# Sheet1.net
KiCad netlist of a schematic drawn in Altium Designer
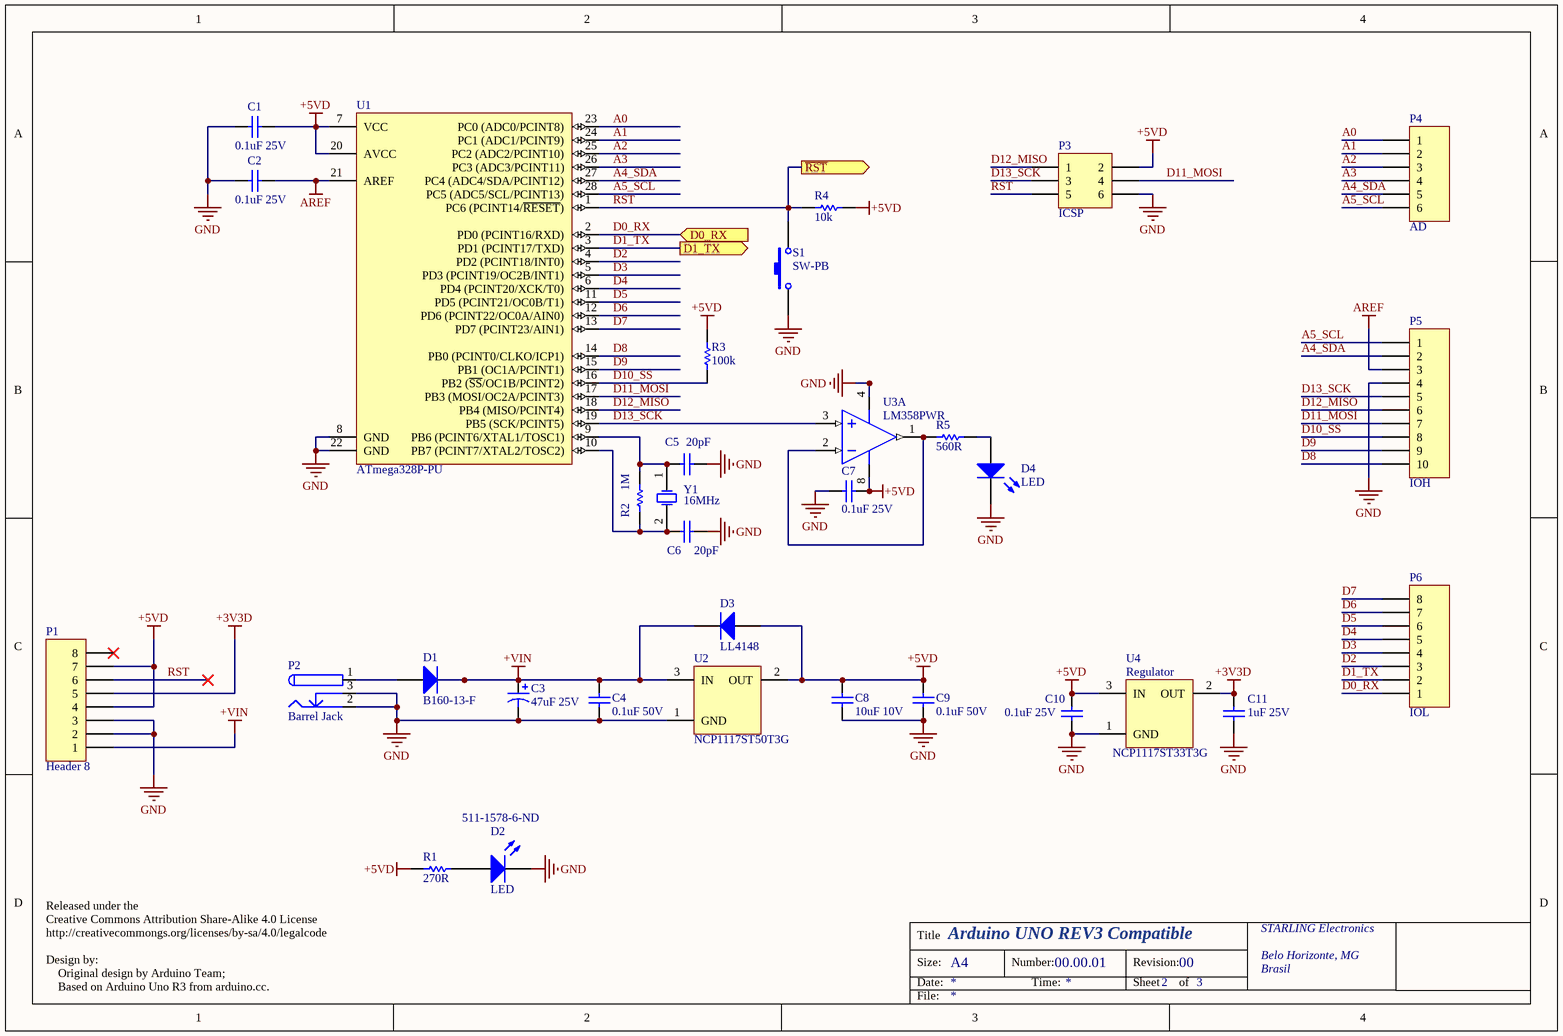
[diagram p0: Sheet1.SchDoc]

(export (version "E")
  (design (tool "Eeschema 10.0.6"))
  (components
    (comp (ref "C1")
      (value "0.1uF 25V")
      (footprint "C1608[0603]")
      (description "Capacitor")
      (fields (field (name "MANUFACTURER PART NUMBER") "GCM188R71E104KA57D") (field (name "TOLERANCE") "10%"))
      (libsource (lib "Basic Library") (part "C"))
    )
    (comp (ref "C2")
      (value "0.1uF 25V")
      (footprint "C1608[0603]")
      (description "Capacitor")
      (fields (field (name "MANUFACTURER PART NUMBER") "GCM188R71E104KA57D") (field (name "TOLERANCE") "10%"))
      (libsource (lib "Basic Library") (part "C"))
    )
    (comp (ref "C3")
      (value "47uF 25V")
      (footprint "Cap_Al_SMD_C6_6.6x6.6mm")
      (description "Polarized Capacitor")
      (fields (field (name "MANUFACTURER PART NUMBER") "EEE-1EA470WP") (field (name "TOLERANCE") "20%"))
      (libsource (lib "Basic Library") (part "CP"))
    )
    (comp (ref "C4")
      (value "0.1uF 50V")
      (footprint "C1608[0603]")
      (description "Capacitor")
      (fields (field (name "MANUFACTURER PART NUMBER") "06035C104KAT2A") (field (name "TOLERANCE") "10%"))
      (libsource (lib "Basic Library") (part "C"))
    )
    (comp (ref "C5")
      (value "20pF")
      (footprint "C1608[0603]")
      (description "Capacitor")
      (fields (field (name "MANUFACTURER PART NUMBER") "CL10C200JB8NNNC") (field (name "TOLERANCE") "5%"))
      (libsource (lib "Basic Library") (part "C"))
    )
    (comp (ref "C6")
      (value "20pF")
      (footprint "C1608[0603]")
      (description "Capacitor")
      (fields (field (name "MANUFACTURER PART NUMBER") "CL10C200JB8NNNC") (field (name "TOLERANCE") "5%"))
      (libsource (lib "Basic Library") (part "C"))
    )
    (comp (ref "C7")
      (value "0.1uF 25V")
      (footprint "C1608[0603]")
      (description "Capacitor")
      (fields (field (name "MANUFACTURER PART NUMBER") "GCM188R71E104KA57D") (field (name "TOLERANCE") "10%"))
      (libsource (lib "Basic Library") (part "C"))
    )
    (comp (ref "C8")
      (value "10uF 10V")
      (footprint "C2012[0805]")
      (description "Capacitor")
      (fields (field (name "MANUFACTURER PART NUMBER") "C0805C106K8PACTU") (field (name "TOLERANCE") "10%"))
      (libsource (lib "Basic Library") (part "C"))
    )
    (comp (ref "C9")
      (value "0.1uF 50V")
      (footprint "C1608[0603]")
      (description "Capacitor")
      (fields (field (name "MANUFACTURER PART NUMBER") "06035C104KAT2A") (field (name "TOLERANCE") "10%"))
      (libsource (lib "Basic Library") (part "C"))
    )
    (comp (ref "C10")
      (value "0.1uF 25V")
      (footprint "C1608[0603]")
      (description "Capacitor")
      (fields (field (name "MANUFACTURER PART NUMBER") "GCM188R71E104KA57D") (field (name "TOLERANCE") "10%"))
      (libsource (lib "Basic Library") (part "C"))
    )
    (comp (ref "C11")
      (value "1uF 25V")
      (footprint "C2012[0805]")
      (description "Capacitor")
      (fields
        (field (name "MANUFACTURER") "TDK")
        (field (name "MANUFACTURER PART NUMBER") "C2012X7R1E105K125AB")
      )
      (libsource (lib "Basic Library") (part "C"))
    )
    (comp (ref "D1")
      (value "B160-13-F")
      (footprint "DO214AC")
      (description "Diode")
      (libsource (lib "Basic Library") (part "D"))
    )
    (comp (ref "D2")
      (value "LED")
      (footprint "LED-0603-G")
      (fields
        (field (name "SUPPLIER PART NUMBER 1") "511-1578-6-ND")
        (field (name "MANUFACTURER PART NUMBER") "SML-D12M8WT86")
      )
      (libsource (lib "Basic Library") (part "LED"))
    )
    (comp (ref "D3")
      (value "LL4148")
      (footprint "SOD-80/MLL34")
      (description "Diode")
      (fields (field (name "VOLTAGE") "100V"))
      (libsource (lib "Basic Library") (part "D"))
    )
    (comp (ref "D4")
      (value "LED")
      (footprint "LED-0603-R")
      (fields (field (name "MANUFACTURER PART NUMBER") "LTST-C191KRKT") (field (name "VOLTAGE") "2V"))
      (libsource (lib "Basic Library") (part "LED"))
    )
    (comp (ref "P1")
      (value "Header 8")
      (footprint "HDR1X8F")
      (description "Header, 8-Pin")
      (fields (field (name "PUBLISHER") "Altium Limited"))
      (libsource (lib "") (part "Header 8_1"))
    )
    (comp (ref "P2")
      (value "Barrel Jack")
      (footprint "BARREL2.5")
      (description "Low Voltage Power Supply Connector")
      (fields
        (field (name "MANUFACTURER") "Memory Protection Devices")
        (field (name "MANUFACTURER PART NUMBER") "EJ503A")
      )
      (libsource (lib "Connectors Library") (part "PWR2.5"))
    )
    (comp (ref "P3")
      (value "ICSP")
      (footprint "HDR2X3M")
      (description "Header, 3-Pin, Dual row")
      (fields
        (field (name "MANUFACTURER") "Harwin")
        (field (name "MANUFACTURER PART NUMBER") "M20-9720345")
        (field (name "PUBLISHER") "Altium Limited")
      )
      (libsource (lib "Connectors Library") (part "Header 3X2"))
    )
    (comp (ref "P4")
      (value "AD")
      (footprint "HDR1X6m")
      (description "Header, 6-Pin")
      (fields (field (name "PUBLISHER") "Altium Limited"))
      (libsource (lib "Connectors Library") (part "Header 6"))
    )
    (comp (ref "P5")
      (value "IOH")
      (footprint "HDR1X10")
      (description "Header, 10-Pin")
      (libsource (lib "Connectors Library") (part "Header 10"))
    )
    (comp (ref "P6")
      (value "IOL")
      (footprint "HDR1X8F")
      (description "Header, 8-Pin")
      (fields
        (field (name "MANUFACTURER") "Sullins")
        (field (name "MANUFACTURER PART NUMBER") "PPTC081LFBN-RC")
        (field (name "PUBLISHER") "Altium Limited")
      )
      (libsource (lib "Connectors Library") (part "Header 8"))
    )
    (comp (ref "R1")
      (value "270R")
      (footprint "R1608[0603]")
      (description "Resistor")
      (fields (field (name "MANUFACTURER PART NUMBER") "CRCW0603270RJNEA") (field (name "TOLERANCE") "5%"))
      (libsource (lib "Basic Library") (part "R"))
    )
    (comp (ref "R2")
      (value "1M")
      (footprint "R2012[0805]")
      (description "Resistor")
      (fields (field (name "MANUFACTURER PART NUMBER") "ERA-6AEB105V") (field (name "TOLERANCE") "1%"))
      (libsource (lib "Basic Library") (part "R"))
    )
    (comp (ref "R3")
      (value "100k")
      (footprint "R1608[0603]")
      (description "Resistor")
      (fields (field (name "MANUFACTURER PART NUMBER") "MCT06030C1003FP500") (field (name "TOLERANCE") "1%"))
      (libsource (lib "Basic Library") (part "R"))
    )
    (comp (ref "R4")
      (value "10k")
      (footprint "R1608[0603]")
      (description "Resistor")
      (fields (field (name "MANUFACTURER PART NUMBER") "MCT06030C1002FP500") (field (name "TOLERANCE") "1%"))
      (libsource (lib "Basic Library") (part "R"))
    )
    (comp (ref "R5")
      (value "560R")
      (footprint "R1608[0603]")
      (description "Resistor")
      (fields (field (name "MANUFACTURER PART NUMBER") "AC0603FR-07560RL") (field (name "TOLERANCE") "1%"))
      (libsource (lib "Basic Library") (part "R"))
    )
    (comp (ref "S1")
      (value "SW-PB")
      (footprint "PB-SW-SMT")
      (description "Tactile Switch")
      (fields (field (name "MANUFACTURER PART NUMBER") "PTS645SM43SMTR92LFS"))
      (libsource (lib "Basic Library") (part "SW Tact"))
    )
    (comp (ref "U1")
      (value "ATmega328P-PU")
      (footprint "DIP28")
      (libsource (lib "Components Library") (part "ATmega328P-PU"))
    )
    (comp (ref "U2")
      (value "NCP1117ST50T3G")
      (footprint "SOT223_N")
      (fields (field (name "TOLERANCE") "1%"))
      (libsource (lib "Basic Library") (part "Regulator"))
    )
    (comp (ref "U3")
      (value "LM358PWR")
      (footprint "TSSOP8-1")
      (fields (field (name "MANUFACTURER") "Texas Instruments"))
      (libsource (lib "Components Library") (part "LM358PWR"))
    )
    (comp (ref "U4")
      (value "Regulator")
      (footprint "SOT223_N")
      (fields
        (field (name "MANUFACTURER") "ON Semiconductor")
        (field (name "MANUFACTURER PART NUMBER") "NCP1117ST33T3G")
      )
      (libsource (lib "Symbols") (part "Regulator"))
    )
    (comp (ref "Y1")
      (value "16MHz")
      (footprint "CRYSTAL-HC49/4H_SMX")
      (description "Crystal Oscillator")
      (fields (field (name "MANUFACTURER PART NUMBER") "ECS-160-20-3X-TR") (field (name "TOLERANCE") "30ppm"))
      (libsource (lib "Basic Library") (part "XTAL"))
    )
  )
  (nets
    (net (code "1") (name "+3V3D") (class "Default")
      (node (ref "C11") (pin "2") (pinfunction "2_2") (pintype "passive"))
      (node (ref "P1") (pin "5") (pinfunction "5_5") (pintype "passive"))
      (node (ref "U4") (pin "2") (pinfunction "OUT_2") (pintype "passive"))
    )
    (net (code "2") (name "+5VD") (class "Default")
      (node (ref "C1") (pin "1") (pinfunction "1_1") (pintype "passive"))
      (node (ref "C10") (pin "2") (pinfunction "2_2") (pintype "passive"))
      (node (ref "C7") (pin "1") (pinfunction "1_1") (pintype "passive"))
      (node (ref "C8") (pin "1") (pinfunction "1_1") (pintype "passive"))
      (node (ref "C9") (pin "1") (pinfunction "1_1") (pintype "passive"))
      (node (ref "D3") (pin "1") (pinfunction "A_1") (pintype "passive"))
      (node (ref "P1") (pin "4") (pinfunction "4_4") (pintype "passive"))
      (node (ref "P1") (pin "7") (pinfunction "7_7") (pintype "passive"))
      (node (ref "P3") (pin "2") (pinfunction "2_2") (pintype "passive"))
      (node (ref "R1") (pin "1") (pinfunction "1_1") (pintype "passive"))
      (node (ref "R3") (pin "1") (pinfunction "1_1") (pintype "passive"))
      (node (ref "R4") (pin "1") (pinfunction "1_1") (pintype "passive"))
      (node (ref "U1") (pin "20") (pinfunction "AVCC_20") (pintype "power_in"))
      (node (ref "U1") (pin "7") (pinfunction "VCC_7") (pintype "power_in"))
      (node (ref "U2") (pin "2") (pinfunction "OUT_2") (pintype "passive"))
      (node (ref "U3") (pin "8") (pinfunction "V+_8") (pintype "power_in"))
      (node (ref "U4") (pin "3") (pinfunction "IN_3") (pintype "passive"))
    )
    (net (code "3") (name "+VIN") (class "Default")
      (node (ref "C3") (pin "1") (pinfunction "1_1") (pintype "passive"))
      (node (ref "C4") (pin "1") (pinfunction "1_1") (pintype "passive"))
      (node (ref "D1") (pin "2") (pinfunction "K_2") (pintype "passive"))
      (node (ref "D3") (pin "2") (pinfunction "K_2") (pintype "passive"))
      (node (ref "P1") (pin "1") (pinfunction "1_1") (pintype "passive"))
      (node (ref "U2") (pin "3") (pinfunction "IN_3") (pintype "passive"))
    )
    (net (code "4") (name "/A0") (class "Default")
      (node (ref "P4") (pin "1") (pinfunction "1_1") (pintype "passive"))
      (node (ref "U1") (pin "23") (pinfunction "PC0_(ADC0/PCINT8)_23") (pintype "bidirectional"))
    )
    (net (code "5") (name "/A1") (class "Default")
      (node (ref "P4") (pin "2") (pinfunction "2_2") (pintype "passive"))
      (node (ref "U1") (pin "24") (pinfunction "PC1_(ADC1/PCINT9)_24") (pintype "bidirectional"))
    )
    (net (code "6") (name "/A2") (class "Default")
      (node (ref "P4") (pin "3") (pinfunction "3_3") (pintype "passive"))
      (node (ref "U1") (pin "25") (pinfunction "PC2_(ADC2/PCINT10)_25") (pintype "bidirectional"))
    )
    (net (code "7") (name "/A3") (class "Default")
      (node (ref "P4") (pin "4") (pinfunction "4_4") (pintype "passive"))
      (node (ref "U1") (pin "26") (pinfunction "PC3_(ADC3/PCINT11)_26") (pintype "bidirectional"))
    )
    (net (code "8") (name "/A4_SDA") (class "Default")
      (node (ref "P4") (pin "5") (pinfunction "5_5") (pintype "passive"))
      (node (ref "P5") (pin "2") (pinfunction "2_2") (pintype "passive"))
      (node (ref "U1") (pin "27") (pinfunction "PC4_(ADC4/SDA/PCINT12)_27") (pintype "bidirectional"))
    )
    (net (code "9") (name "/A5_SCL") (class "Default")
      (node (ref "P4") (pin "6") (pinfunction "6_6") (pintype "passive"))
      (node (ref "P5") (pin "1") (pinfunction "1_1") (pintype "passive"))
      (node (ref "U1") (pin "28") (pinfunction "PC5_(ADC5/SCL/PCINT13)_28") (pintype "bidirectional"))
    )
    (net (code "10") (name "/D0_RX") (class "Default")
      (node (ref "P6") (pin "1") (pinfunction "1_1") (pintype "passive"))
      (node (ref "U1") (pin "2") (pinfunction "PD0_(PCINT16/RXD)_2") (pintype "bidirectional"))
    )
    (net (code "11") (name "/D1_TX") (class "Default")
      (node (ref "P6") (pin "2") (pinfunction "2_2") (pintype "passive"))
      (node (ref "U1") (pin "3") (pinfunction "PD1_(PCINT17/TXD)_3") (pintype "bidirectional"))
    )
    (net (code "12") (name "/D2") (class "Default")
      (node (ref "P6") (pin "3") (pinfunction "3_3") (pintype "passive"))
      (node (ref "U1") (pin "4") (pinfunction "PD2_(PCINT18/INT0)_4") (pintype "bidirectional"))
    )
    (net (code "13") (name "/D3") (class "Default")
      (node (ref "P6") (pin "4") (pinfunction "4_4") (pintype "passive"))
      (node (ref "U1") (pin "5") (pinfunction "PD3_(PCINT19/OC2B/INT1)_5") (pintype "bidirectional"))
    )
    (net (code "14") (name "/D4") (class "Default")
      (node (ref "P6") (pin "5") (pinfunction "5_5") (pintype "passive"))
      (node (ref "U1") (pin "6") (pinfunction "PD4_(PCINT20/XCK/T0)_6") (pintype "bidirectional"))
    )
    (net (code "15") (name "/D5") (class "Default")
      (node (ref "P6") (pin "6") (pinfunction "6_6") (pintype "passive"))
      (node (ref "U1") (pin "11") (pinfunction "PD5_(PCINT21/OC0B/T1)_11") (pintype "bidirectional"))
    )
    (net (code "16") (name "/D6") (class "Default")
      (node (ref "P6") (pin "7") (pinfunction "7_7") (pintype "passive"))
      (node (ref "U1") (pin "12") (pinfunction "PD6_(PCINT22/OC0A/AIN0)_12") (pintype "bidirectional"))
    )
    (net (code "17") (name "/D7") (class "Default")
      (node (ref "P6") (pin "8") (pinfunction "8_8") (pintype "passive"))
      (node (ref "U1") (pin "13") (pinfunction "PD7_(PCINT23/AIN1)_13") (pintype "bidirectional"))
    )
    (net (code "18") (name "/D8") (class "Default")
      (node (ref "P5") (pin "10") (pinfunction "10_10") (pintype "passive"))
      (node (ref "U1") (pin "14") (pinfunction "PB0_(PCINT0/CLKO/ICP1)_14") (pintype "bidirectional"))
    )
    (net (code "19") (name "/D9") (class "Default")
      (node (ref "P5") (pin "9") (pinfunction "9_9") (pintype "passive"))
      (node (ref "U1") (pin "15") (pinfunction "PB1_(OC1A/PCINT1)_15") (pintype "bidirectional"))
    )
    (net (code "20") (name "/D10_SS") (class "Default")
      (node (ref "P5") (pin "8") (pinfunction "8_8") (pintype "passive"))
      (node (ref "R3") (pin "2") (pinfunction "2_2") (pintype "passive"))
      (node (ref "U1") (pin "16") (pinfunction "PB2_(~{SS}/OC1B/PCINT2)_16") (pintype "bidirectional"))
    )
    (net (code "21") (name "/D11_MOSI") (class "Default")
      (node (ref "P3") (pin "4") (pinfunction "4_4") (pintype "passive"))
      (node (ref "P5") (pin "7") (pinfunction "7_7") (pintype "passive"))
      (node (ref "U1") (pin "17") (pinfunction "PB3_(MOSI/OC2A/PCINT3)_17") (pintype "bidirectional"))
    )
    (net (code "22") (name "/D12_MISO") (class "Default")
      (node (ref "P3") (pin "1") (pinfunction "1_1") (pintype "passive"))
      (node (ref "P5") (pin "6") (pinfunction "6_6") (pintype "passive"))
      (node (ref "U1") (pin "18") (pinfunction "PB4_(MISO/PCINT4)_18") (pintype "bidirectional"))
    )
    (net (code "23") (name "/D13_SCK") (class "Default")
      (node (ref "P3") (pin "3") (pinfunction "3_3") (pintype "passive"))
      (node (ref "P5") (pin "5") (pinfunction "5_5") (pintype "passive"))
      (node (ref "U1") (pin "19") (pinfunction "PB5_(SCK/PCINT5)_19") (pintype "bidirectional"))
      (node (ref "U3") (pin "3") (pinfunction "IN+_3") (pintype "input"))
    )
    (net (code "24") (name "/RST") (class "Default")
      (node (ref "P1") (pin "6") (pinfunction "6_6") (pintype "passive+no_connect"))
    )
    (net (code "25") (name "/~{RST}") (class "Default")
      (node (ref "P3") (pin "5") (pinfunction "5_5") (pintype "passive"))
      (node (ref "R4") (pin "2") (pinfunction "2_2") (pintype "passive"))
      (node (ref "S1") (pin "2") (pinfunction "2_2") (pintype "passive"))
      (node (ref "U1") (pin "1") (pinfunction "PC6_(PCINT14/~{RESET})_1") (pintype "bidirectional"))
    )
    (net (code "26") (name "AREF") (class "Default")
      (node (ref "C2") (pin "1") (pinfunction "1_1") (pintype "passive"))
      (node (ref "P5") (pin "3") (pinfunction "3_3") (pintype "passive"))
      (node (ref "U1") (pin "21") (pinfunction "AREF_21") (pintype "power_in"))
    )
    (net (code "27") (name "GND") (class "Default")
      (node (ref "C1") (pin "2") (pinfunction "2_2") (pintype "passive"))
      (node (ref "C10") (pin "1") (pinfunction "1_1") (pintype "passive"))
      (node (ref "C11") (pin "1") (pinfunction "1_1") (pintype "passive"))
      (node (ref "C2") (pin "2") (pinfunction "2_2") (pintype "passive"))
      (node (ref "C3") (pin "2") (pinfunction "2_2") (pintype "passive"))
      (node (ref "C4") (pin "2") (pinfunction "2_2") (pintype "passive"))
      (node (ref "C5") (pin "2") (pinfunction "2_2") (pintype "passive"))
      (node (ref "C6") (pin "2") (pinfunction "2_2") (pintype "passive"))
      (node (ref "C7") (pin "2") (pinfunction "2_2") (pintype "passive"))
      (node (ref "C8") (pin "2") (pinfunction "2_2") (pintype "passive"))
      (node (ref "C9") (pin "2") (pinfunction "2_2") (pintype "passive"))
      (node (ref "D2") (pin "2") (pinfunction "K_2") (pintype "passive"))
      (node (ref "D4") (pin "2") (pinfunction "K_2") (pintype "passive"))
      (node (ref "P1") (pin "2") (pinfunction "2_2") (pintype "passive"))
      (node (ref "P1") (pin "3") (pinfunction "3_3") (pintype "passive"))
      (node (ref "P2") (pin "2") (pinfunction "2_2") (pintype "passive"))
      (node (ref "P2") (pin "3") (pinfunction "3_3") (pintype "passive"))
      (node (ref "P3") (pin "6") (pinfunction "6_6") (pintype "passive"))
      (node (ref "P5") (pin "4") (pinfunction "4_4") (pintype "passive"))
      (node (ref "S1") (pin "1") (pinfunction "1_1") (pintype "passive"))
      (node (ref "U1") (pin "22") (pinfunction "GND_22") (pintype "power_in"))
      (node (ref "U1") (pin "8") (pinfunction "GND_8") (pintype "power_in"))
      (node (ref "U2") (pin "1") (pinfunction "GND_1") (pintype "passive"))
      (node (ref "U3") (pin "4") (pinfunction "V-_4") (pintype "power_in"))
      (node (ref "U4") (pin "1") (pinfunction "GND_1") (pintype "passive"))
    )
    (net (code "28") (name "Net-(D1-A)") (class "Default")
      (node (ref "D1") (pin "1") (pinfunction "A_1") (pintype "passive"))
      (node (ref "P2") (pin "1") (pinfunction "1_1") (pintype "passive"))
    )
    (net (code "29") (name "Net-(D2-A)") (class "Default")
      (node (ref "D2") (pin "1") (pinfunction "A_1") (pintype "passive"))
      (node (ref "R1") (pin "2") (pinfunction "2_2") (pintype "passive"))
    )
    (net (code "30") (name "Net-(D4-A)") (class "Default")
      (node (ref "D4") (pin "1") (pinfunction "A_1") (pintype "passive"))
      (node (ref "R5") (pin "2") (pinfunction "2_2") (pintype "passive"))
    )
    (net (code "31") (name "Net-(U1-PB6_(PCINT6{slash}XTAL1{slash}TOSC1))") (class "Default")
      (node (ref "C5") (pin "1") (pinfunction "1_1") (pintype "passive"))
      (node (ref "R2") (pin "2") (pinfunction "2_2") (pintype "passive"))
      (node (ref "U1") (pin "9") (pinfunction "PB6_(PCINT6/XTAL1/TOSC1)_9") (pintype "bidirectional"))
      (node (ref "Y1") (pin "1") (pinfunction "OSC1_1") (pintype "passive"))
    )
    (net (code "32") (name "Net-(U1-PB7_(PCINT7{slash}XTAL2{slash}TOSC2))") (class "Default")
      (node (ref "C6") (pin "1") (pinfunction "1_1") (pintype "passive"))
      (node (ref "R2") (pin "1") (pinfunction "1_1") (pintype "passive"))
      (node (ref "U1") (pin "10") (pinfunction "PB7_(PCINT7/XTAL2/TOSC2)_10") (pintype "bidirectional"))
      (node (ref "Y1") (pin "2") (pinfunction "OSC2_2") (pintype "passive"))
    )
    (net (code "33") (name "Net-(U3A-IN-)") (class "Default")
      (node (ref "R5") (pin "1") (pinfunction "1_1") (pintype "passive"))
      (node (ref "U3") (pin "1") (pinfunction "OUT_1") (pintype "output"))
      (node (ref "U3") (pin "2") (pinfunction "IN-_2") (pintype "input"))
    )
    (net (code "34") (name "unconnected-(P1-Pad8)") (class "Default")
      (node (ref "P1") (pin "8") (pinfunction "8_8") (pintype "passive+no_connect"))
    )
  )
)
